# Driver.net
KiCad netlist of a schematic drawn in EAGLE
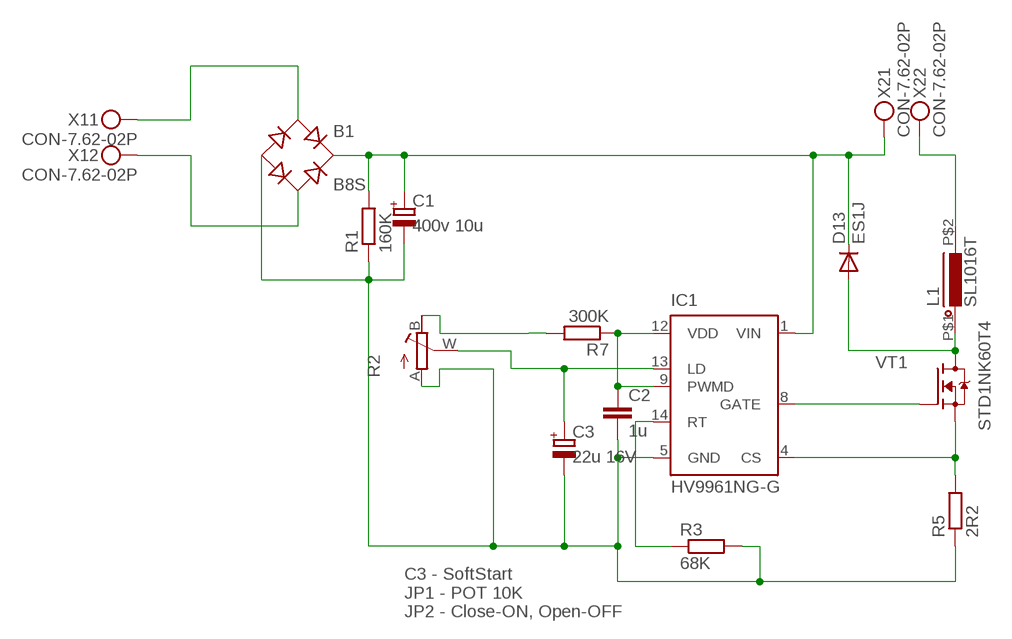
[diagram p0: schematic, sheet 1]

(export (version "E")
  (design (tool "Eeschema 10.0.6"))
  (components
    (comp (ref "B1")
      (value "B8S")
      (footprint "eagle-import:DFS")
      (libsource (lib "eagle-import") (part "DFS01"))
    )
    (comp (ref "C1")
      (value "400v 10u")
      (footprint "eagle-import:E3,5-8")
      (libsource (lib "eagle-import") (part "CAP-POL_E3.5-8"))
    )
    (comp (ref "C2")
      (value "1u")
      (footprint "eagle-import:C0805")
      (libsource (lib "eagle-import") (part "CAP_0805"))
    )
    (comp (ref "C3")
      (value "22u 16V")
      (footprint "eagle-import:CT3528")
      (libsource (lib "eagle-import") (part "CAP-POL_3528"))
    )
    (comp (ref "D13")
      (value "ES1J")
      (footprint "eagle-import:DO214AC")
      (libsource (lib "eagle-import") (part "DIODE_ES1J"))
    )
    (comp (ref "IC1")
      (value "HV9961NG-G")
      (footprint "eagle-import:SOIC-16NG")
      (libsource (lib "eagle-import") (part "HV9910BNG"))
    )
    (comp (ref "L1")
      (value "SL1016T")
      (footprint "eagle-import:SL1016")
      (libsource (lib "eagle-import") (part "INDUCTORSL1016"))
    )
    (comp (ref "R1")
      (value "160K")
      (footprint "eagle-import:MF-0125")
      (libsource (lib "eagle-import") (part "Namenlos_R_MF-0125"))
    )
    (comp (ref "R2")
      (value "R_POTTURN-X")
      (footprint "eagle-import:RJ9W")
      (libsource (lib "eagle-import") (part "R_POTTURN-X"))
    )
    (comp (ref "R3")
      (value "68K")
      (footprint "eagle-import:R0805")
      (libsource (lib "eagle-import") (part "Namenlos_R_0805"))
    )
    (comp (ref "R5")
      (value "2R2")
      (footprint "eagle-import:MF-05")
      (libsource (lib "eagle-import") (part "R_MF-05"))
    )
    (comp (ref "R7")
      (value "300K")
      (footprint "eagle-import:R0805")
      (libsource (lib "eagle-import") (part "Namenlos_R_0805"))
    )
    (comp (ref "VT1")
      (value "STD1NK60T4")
      (footprint "eagle-import:DPAK")
      (libsource (lib "eagle-import") (part "FET-NDPAK"))
    )
    (comp (ref "X1")
      (value "CON-7.62-02P")
      (footprint "eagle-import:KF25C-7.62-02P-13")
      (libsource (lib "eagle-import") (part "CON-7.62-02P"))
    )
    (comp (ref "X2")
      (value "CON-7.62-02P")
      (footprint "eagle-import:KF25C-7.62-02P-13")
      (libsource (lib "eagle-import") (part "CON-7.62-02P"))
    )
  )
  (nets
    (net (code "1") (name "Net-(IC1-CS)") (class "Default")
      (node (ref "IC1") (pin "4") (pinfunction "CS_4") (pintype "input"))
      (node (ref "R5") (pin "2") (pinfunction "2_2") (pintype "passive"))
      (node (ref "VT1") (pin "S") (pinfunction "S_S") (pintype "passive"))
    )
    (net (code "2") (name "Net-(IC1-GATE)") (class "Default")
      (node (ref "IC1") (pin "8") (pinfunction "GATE_8") (pintype "output"))
      (node (ref "VT1") (pin "G") (pinfunction "G_G") (pintype "passive"))
    )
    (net (code "3") (name "Net-(IC1-GND)") (class "Default")
      (node (ref "B1") (pin "-") (pinfunction "-_-") (pintype "passive"))
      (node (ref "C1") (pin "-") (pinfunction "-_-") (pintype "passive"))
      (node (ref "C2") (pin "2") (pinfunction "2_2") (pintype "passive"))
      (node (ref "C3") (pin "-") (pinfunction "-_-") (pintype "passive"))
      (node (ref "IC1") (pin "5") (pinfunction "GND_5") (pintype "power_in"))
      (node (ref "R1") (pin "1") (pinfunction "1_1") (pintype "passive"))
      (node (ref "R2") (pin "A") (pinfunction "A_A") (pintype "passive"))
      (node (ref "R3") (pin "2") (pinfunction "2_2") (pintype "passive"))
      (node (ref "R5") (pin "1") (pinfunction "1_1") (pintype "passive"))
    )
    (net (code "4") (name "Net-(IC1-LD)") (class "Default")
      (node (ref "C3") (pin "+") (pinfunction "+_+") (pintype "passive"))
      (node (ref "IC1") (pin "13") (pinfunction "LD_13") (pintype "input"))
      (node (ref "R2") (pin "W") (pinfunction "S_W") (pintype "passive"))
    )
    (net (code "5") (name "Net-(IC1-PWMD)") (class "Default")
      (node (ref "C2") (pin "1") (pinfunction "1_1") (pintype "passive"))
      (node (ref "IC1") (pin "12") (pinfunction "VDD_12") (pintype "power_in"))
      (node (ref "IC1") (pin "9") (pinfunction "PWMD_9") (pintype "input"))
      (node (ref "R7") (pin "1") (pinfunction "1_1") (pintype "passive"))
    )
    (net (code "6") (name "Net-(IC1-RT)") (class "Default")
      (node (ref "IC1") (pin "14") (pinfunction "RT_14") (pintype "passive"))
      (node (ref "R3") (pin "1") (pinfunction "1_1") (pintype "passive"))
    )
    (net (code "7") (name "Net-(IC1-VIN)") (class "Default")
      (node (ref "B1") (pin "+") (pinfunction "+_+") (pintype "passive"))
      (node (ref "C1") (pin "+") (pinfunction "+_+") (pintype "passive"))
      (node (ref "D13") (pin "C") (pinfunction "C_C") (pintype "passive"))
      (node (ref "IC1") (pin "1") (pinfunction "VIN_1") (pintype "input"))
      (node (ref "R1") (pin "2") (pinfunction "2_2") (pintype "passive"))
      (node (ref "X2") (pin "P$1") (pinfunction "KL_P$1") (pintype "passive"))
    )
    (net (code "8") (name "Net-(L1-1)") (class "Default")
      (node (ref "D13") (pin "A") (pinfunction "A_A") (pintype "passive"))
      (node (ref "L1") (pin "P$1") (pinfunction "1_P$1") (pintype "passive"))
      (node (ref "VT1") (pin "D") (pinfunction "D_D") (pintype "passive"))
    )
    (net (code "9") (name "Net-(L1-2)") (class "Default")
      (node (ref "L1") (pin "P$2") (pinfunction "2_P$2") (pintype "passive"))
      (node (ref "X2") (pin "P$2") (pinfunction "KL_P$2") (pintype "passive"))
    )
    (net (code "10") (name "Net-(R2-E)") (class "Default")
      (node (ref "R2") (pin "B") (pinfunction "E_B") (pintype "passive"))
      (node (ref "R7") (pin "2") (pinfunction "2_2") (pintype "passive"))
    )
    (net (code "11") (name "Net-(X1A-KL)") (class "Default")
      (node (ref "B1") (pin "AC1") (pinfunction "AC1_AC1") (pintype "passive"))
      (node (ref "X1") (pin "P$1") (pinfunction "KL_P$1") (pintype "passive"))
    )
    (net (code "12") (name "Net-(X1B-KL)") (class "Default")
      (node (ref "B1") (pin "AC2") (pinfunction "AC2_AC2") (pintype "passive"))
      (node (ref "X1") (pin "P$2") (pinfunction "KL_P$2") (pintype "passive"))
    )
  )
)
